# WaveFolder.net
KiCad netlist of a schematic drawn in EAGLE
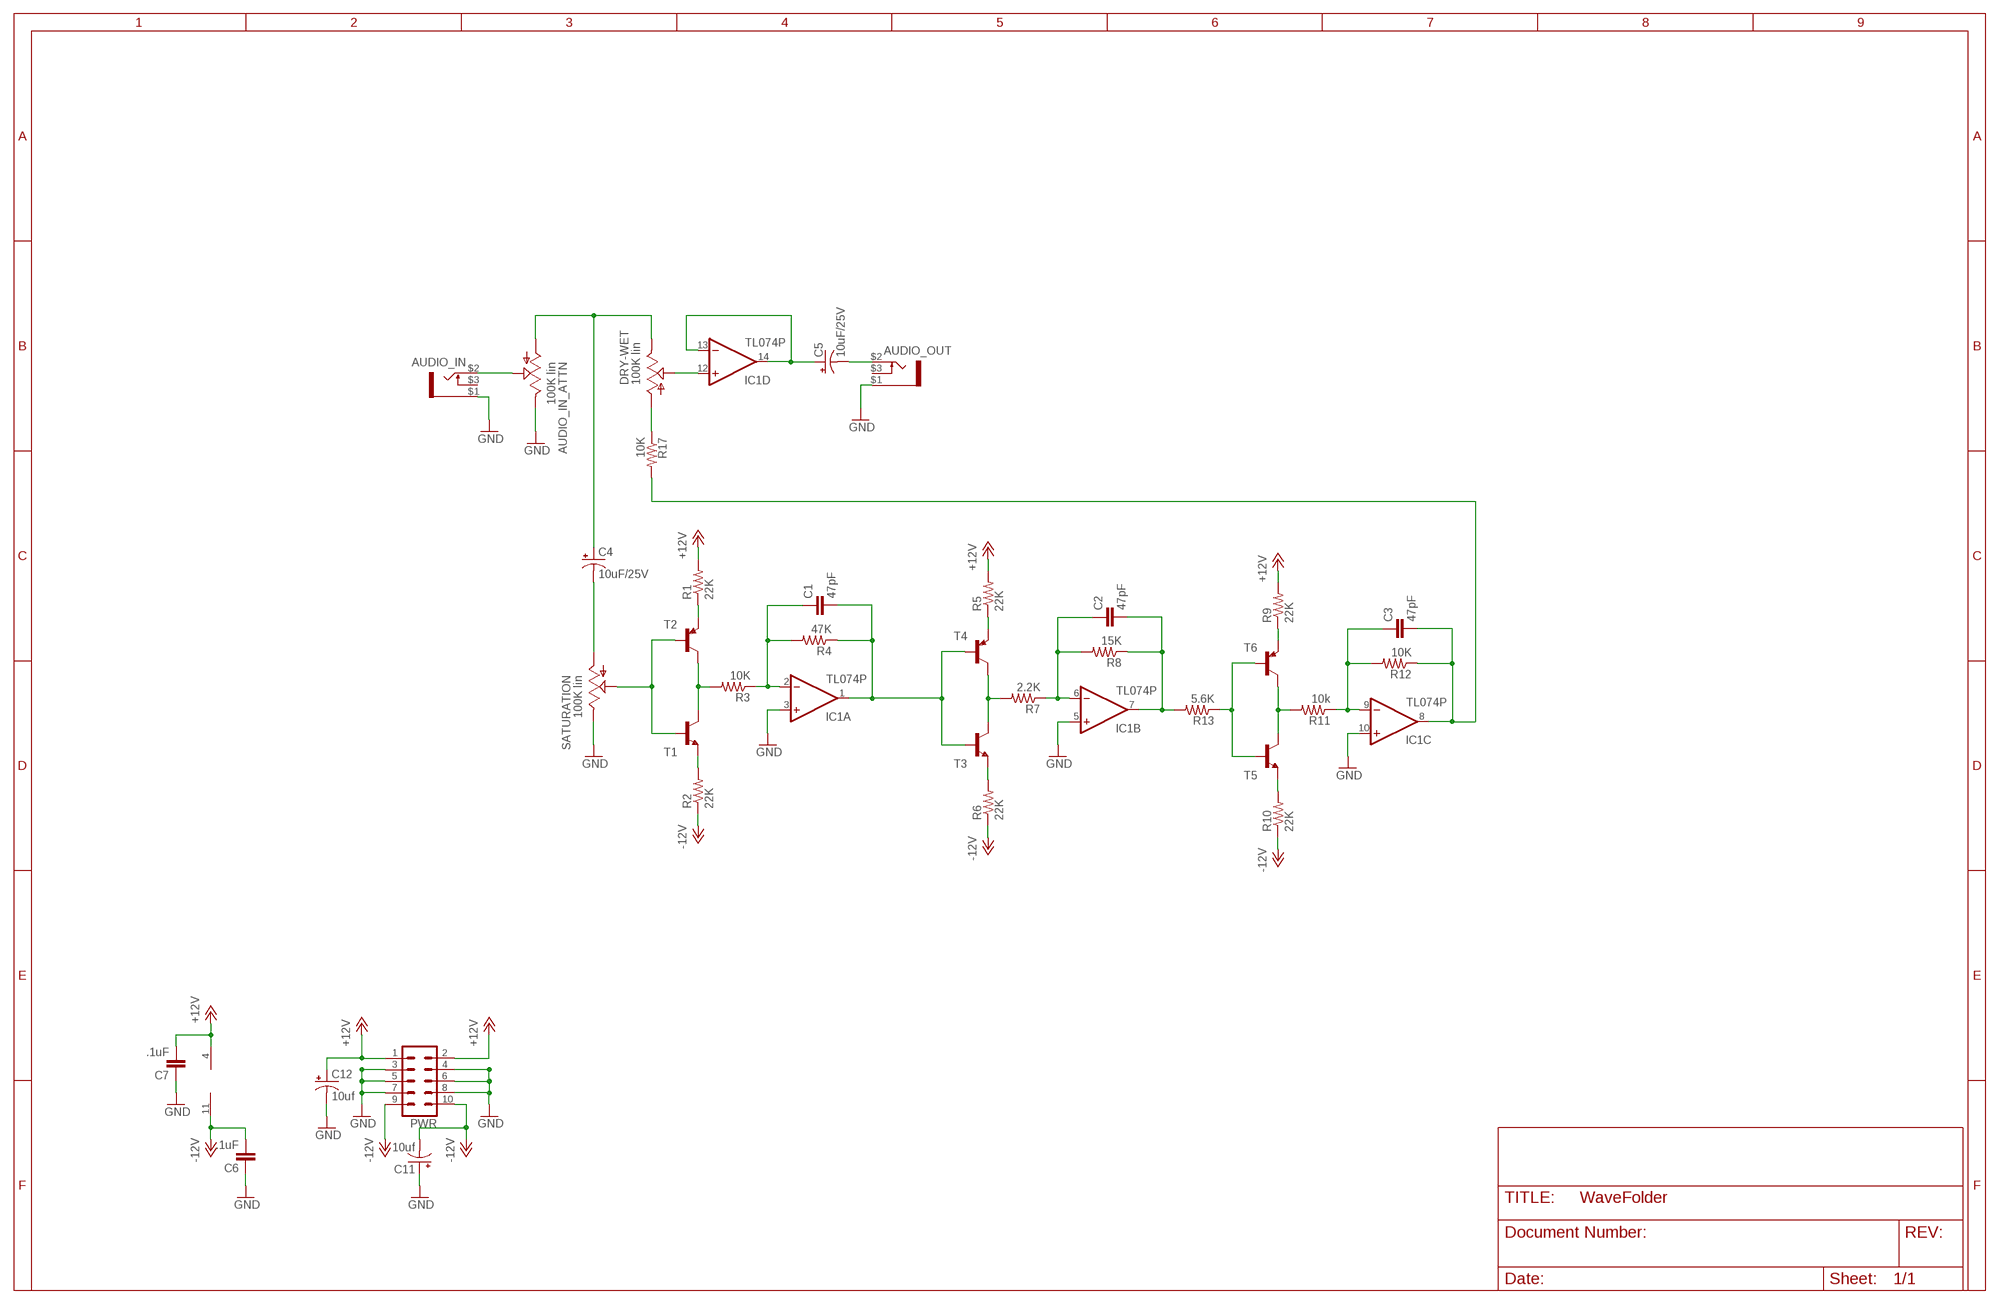
[diagram p0: schematic, sheet 1]

(export (version "E")
  (design (tool "Eeschema 10.0.6"))
  (components
    (comp (ref "AUDIO_IN")
      (value "PJ-323PJ-323")
      (footprint "eagle-import:PJ-323")
      (libsource (lib "eagle-import") (part "PJ-323PJ-323"))
    )
    (comp (ref "AUDIO_IN_ATTN")
      (value "100K lin")
      (footprint "eagle-import:EVUF")
      (libsource (lib "eagle-import") (part "RIGHT-ANGLE-POTA"))
    )
    (comp (ref "AUDIO_OUT")
      (value "PJ-323PJ-323")
      (footprint "eagle-import:PJ-323")
      (libsource (lib "eagle-import") (part "PJ-323PJ-323"))
    )
    (comp (ref "C1")
      (value "47pF")
      (footprint "eagle-import:C025-024X044")
      (libsource (lib "eagle-import") (part "C-EU025-024X044"))
    )
    (comp (ref "C2")
      (value "47pF")
      (footprint "eagle-import:C025-024X044")
      (libsource (lib "eagle-import") (part "C-EU025-024X044"))
    )
    (comp (ref "C3")
      (value "47pF")
      (footprint "eagle-import:C025-024X044")
      (libsource (lib "eagle-import") (part "C-EU025-024X044"))
    )
    (comp (ref "C4")
      (value "10uF/25V")
      (footprint "eagle-import:E2,5-6")
      (libsource (lib "eagle-import") (part "CPOL-USE2.5-6"))
    )
    (comp (ref "C5")
      (value "10uF/25V")
      (footprint "eagle-import:E2,5-6")
      (libsource (lib "eagle-import") (part "CPOL-USE2.5-6"))
    )
    (comp (ref "C6")
      (value ".1uF")
      (footprint "eagle-import:C025-024X044")
      (libsource (lib "eagle-import") (part "C-EU025-024X044"))
    )
    (comp (ref "C7")
      (value ".1uF")
      (footprint "eagle-import:C025-024X044")
      (libsource (lib "eagle-import") (part "C-EU025-024X044"))
    )
    (comp (ref "C11")
      (value "10uf")
      (footprint "eagle-import:E2,5-5")
      (libsource (lib "eagle-import") (part "resistor_CPOL-USE2.5-5"))
    )
    (comp (ref "C12")
      (value "10uf")
      (footprint "eagle-import:E2,5-5")
      (libsource (lib "eagle-import") (part "resistor_CPOL-USE2.5-5"))
    )
    (comp (ref "DRY-WET")
      (value "100K lin")
      (footprint "eagle-import:EVUF")
      (libsource (lib "eagle-import") (part "RIGHT-ANGLE-POTA"))
    )
    (comp (ref "IC1")
      (value "TL074P")
      (footprint "eagle-import:DIL14")
      (libsource (lib "eagle-import") (part "TL074P"))
    )
    (comp (ref "PWR")
      (value "ML10")
      (footprint "eagle-import:ML10")
      (libsource (lib "eagle-import") (part "ML10"))
    )
    (comp (ref "R1")
      (value "22K")
      (footprint "eagle-import:0207_7")
      (libsource (lib "eagle-import") (part "R-US_0207/7"))
    )
    (comp (ref "R2")
      (value "22K")
      (footprint "eagle-import:0207_7")
      (libsource (lib "eagle-import") (part "R-US_0207/7"))
    )
    (comp (ref "R3")
      (value "10K")
      (footprint "eagle-import:0207_7")
      (libsource (lib "eagle-import") (part "R-US_0207/7"))
    )
    (comp (ref "R4")
      (value "47K")
      (footprint "eagle-import:0207_7")
      (libsource (lib "eagle-import") (part "R-US_0207/7"))
    )
    (comp (ref "R5")
      (value "22K")
      (footprint "eagle-import:0207_7")
      (libsource (lib "eagle-import") (part "R-US_0207/7"))
    )
    (comp (ref "R6")
      (value "22K")
      (footprint "eagle-import:0207_7")
      (libsource (lib "eagle-import") (part "R-US_0207/7"))
    )
    (comp (ref "R7")
      (value "2.2K")
      (footprint "eagle-import:0207_7")
      (libsource (lib "eagle-import") (part "R-US_0207/7"))
    )
    (comp (ref "R8")
      (value "15K")
      (footprint "eagle-import:0207_7")
      (libsource (lib "eagle-import") (part "R-US_0207/7"))
    )
    (comp (ref "R9")
      (value "22K")
      (footprint "eagle-import:0207_7")
      (libsource (lib "eagle-import") (part "R-US_0207/7"))
    )
    (comp (ref "R10")
      (value "22K")
      (footprint "eagle-import:0207_7")
      (libsource (lib "eagle-import") (part "R-US_0207/7"))
    )
    (comp (ref "R11")
      (value "10k")
      (footprint "eagle-import:0207_7")
      (libsource (lib "eagle-import") (part "R-US_0207/7"))
    )
    (comp (ref "R12")
      (value "10K")
      (footprint "eagle-import:0207_7")
      (libsource (lib "eagle-import") (part "R-US_0207/7"))
    )
    (comp (ref "R13")
      (value "5.6K")
      (footprint "eagle-import:0207_7")
      (libsource (lib "eagle-import") (part "R-US_0207/7"))
    )
    (comp (ref "R17")
      (value "10K")
      (footprint "eagle-import:0207_7")
      (libsource (lib "eagle-import") (part "R-US_0207/7"))
    )
    (comp (ref "SATURATION")
      (value "100K lin")
      (footprint "eagle-import:EVUF")
      (libsource (lib "eagle-import") (part "RIGHT-ANGLE-POTA"))
    )
    (comp (ref "T1")
      (value "2N3904-NPN-TO92-EBC")
      (footprint "eagle-import:TO92-EBC")
      (libsource (lib "eagle-import") (part "-NPN-TO92-EBC2N3904"))
    )
    (comp (ref "T2")
      (value "2N3906-PNP-TO92-EBC")
      (footprint "eagle-import:TO92-EBC")
      (libsource (lib "eagle-import") (part "-PNP-TO92-EBC2N3906"))
    )
    (comp (ref "T3")
      (value "2N3904-NPN-TO92-EBC")
      (footprint "eagle-import:TO92-EBC")
      (libsource (lib "eagle-import") (part "-NPN-TO92-EBC2N3904"))
    )
    (comp (ref "T4")
      (value "2N3906-PNP-TO92-EBC")
      (footprint "eagle-import:TO92-EBC")
      (libsource (lib "eagle-import") (part "-PNP-TO92-EBC2N3906"))
    )
    (comp (ref "T5")
      (value "2N3904-NPN-TO92-EBC")
      (footprint "eagle-import:TO92-EBC")
      (libsource (lib "eagle-import") (part "-NPN-TO92-EBC2N3904"))
    )
    (comp (ref "T6")
      (value "2N3906-PNP-TO92-EBC")
      (footprint "eagle-import:TO92-EBC")
      (libsource (lib "eagle-import") (part "-PNP-TO92-EBC2N3906"))
    )
  )
  (nets
    (net (code "1") (name "+12V") (class "Default")
      (node (ref "C12") (pin "+") (pinfunction "+_+") (pintype "passive"))
      (node (ref "C7") (pin "2") (pinfunction "2_2") (pintype "passive"))
      (node (ref "IC1") (pin "4") (pinfunction "V+_4") (pintype "power_in"))
      (node (ref "PWR") (pin "1") (pinfunction "1_1") (pintype "passive"))
      (node (ref "PWR") (pin "2") (pinfunction "2_2") (pintype "passive"))
      (node (ref "R1") (pin "2") (pinfunction "2_2") (pintype "passive"))
      (node (ref "R5") (pin "2") (pinfunction "2_2") (pintype "passive"))
      (node (ref "R9") (pin "2") (pinfunction "2_2") (pintype "passive"))
    )
    (net (code "2") (name "-12V") (class "Default")
      (node (ref "C11") (pin "-") (pinfunction "-_-") (pintype "passive"))
      (node (ref "C6") (pin "2") (pinfunction "2_2") (pintype "passive"))
      (node (ref "IC1") (pin "11") (pinfunction "V-_11") (pintype "power_in"))
      (node (ref "PWR") (pin "10") (pinfunction "10_10") (pintype "passive"))
      (node (ref "PWR") (pin "9") (pinfunction "9_9") (pintype "passive"))
      (node (ref "R10") (pin "1") (pinfunction "1_1") (pintype "passive"))
      (node (ref "R2") (pin "1") (pinfunction "1_1") (pintype "passive"))
      (node (ref "R6") (pin "1") (pinfunction "1_1") (pintype "passive"))
    )
    (net (code "3") (name "GND") (class "Default")
      (node (ref "AUDIO_IN") (pin "$1") (pinfunction "3_$1") (pintype "passive"))
      (node (ref "AUDIO_IN_ATTN") (pin "3") (pinfunction "E_3") (pintype "passive"))
      (node (ref "AUDIO_OUT") (pin "$1") (pinfunction "3_$1") (pintype "passive"))
      (node (ref "C11") (pin "+") (pinfunction "+_+") (pintype "passive"))
      (node (ref "C12") (pin "-") (pinfunction "-_-") (pintype "passive"))
      (node (ref "C6") (pin "1") (pinfunction "1_1") (pintype "passive"))
      (node (ref "C7") (pin "1") (pinfunction "1_1") (pintype "passive"))
      (node (ref "IC1") (pin "10") (pinfunction "+IN_10") (pintype "input"))
      (node (ref "IC1") (pin "3") (pinfunction "+IN_3") (pintype "input"))
      (node (ref "IC1") (pin "5") (pinfunction "+IN_5") (pintype "input"))
      (node (ref "PWR") (pin "3") (pinfunction "3_3") (pintype "passive"))
      (node (ref "PWR") (pin "4") (pinfunction "4_4") (pintype "passive"))
      (node (ref "PWR") (pin "5") (pinfunction "5_5") (pintype "passive"))
      (node (ref "PWR") (pin "6") (pinfunction "6_6") (pintype "passive"))
      (node (ref "PWR") (pin "7") (pinfunction "7_7") (pintype "passive"))
      (node (ref "PWR") (pin "8") (pinfunction "8_8") (pintype "passive"))
      (node (ref "SATURATION") (pin "3") (pinfunction "E_3") (pintype "passive"))
    )
    (net (code "4") (name "Net-(AUDIO_IN-1)") (class "Default")
      (node (ref "AUDIO_IN") (pin "$2") (pinfunction "1_$2") (pintype "passive"))
      (node (ref "AUDIO_IN_ATTN") (pin "2") (pinfunction "S_2") (pintype "passive"))
    )
    (net (code "5") (name "Net-(AUDIO_IN_ATTN-A)") (class "Default")
      (node (ref "AUDIO_IN_ATTN") (pin "1") (pinfunction "A_1") (pintype "passive"))
      (node (ref "C4") (pin "+") (pinfunction "+_+") (pintype "passive"))
      (node (ref "DRY-WET") (pin "3") (pinfunction "E_3") (pintype "passive"))
    )
    (net (code "6") (name "Net-(AUDIO_OUT-1)") (class "Default")
      (node (ref "AUDIO_OUT") (pin "$2") (pinfunction "1_$2") (pintype "passive"))
      (node (ref "C5") (pin "-") (pinfunction "-_-") (pintype "passive"))
    )
    (net (code "7") (name "Net-(DRY-WET-A)") (class "Default")
      (node (ref "DRY-WET") (pin "1") (pinfunction "A_1") (pintype "passive"))
      (node (ref "R17") (pin "1") (pinfunction "1_1") (pintype "passive"))
    )
    (net (code "8") (name "Net-(DRY-WET-S)") (class "Default")
      (node (ref "DRY-WET") (pin "2") (pinfunction "S_2") (pintype "passive"))
      (node (ref "IC1") (pin "12") (pinfunction "+IN_12") (pintype "input"))
    )
    (net (code "9") (name "Net-(IC1A--IN)") (class "Default")
      (node (ref "C1") (pin "1") (pinfunction "1_1") (pintype "passive"))
      (node (ref "IC1") (pin "2") (pinfunction "-IN_2") (pintype "input"))
      (node (ref "R3") (pin "1") (pinfunction "1_1") (pintype "passive"))
      (node (ref "R4") (pin "2") (pinfunction "2_2") (pintype "passive"))
    )
    (net (code "10") (name "Net-(IC1A-OUT)") (class "Default")
      (node (ref "C1") (pin "2") (pinfunction "2_2") (pintype "passive"))
      (node (ref "IC1") (pin "1") (pinfunction "OUT_1") (pintype "output"))
      (node (ref "R4") (pin "1") (pinfunction "1_1") (pintype "passive"))
      (node (ref "T3") (pin "B") (pinfunction "B_B") (pintype "passive"))
      (node (ref "T4") (pin "B") (pinfunction "B_B") (pintype "passive"))
    )
    (net (code "11") (name "Net-(IC1B--IN)") (class "Default")
      (node (ref "C2") (pin "1") (pinfunction "1_1") (pintype "passive"))
      (node (ref "IC1") (pin "6") (pinfunction "-IN_6") (pintype "input"))
      (node (ref "R7") (pin "1") (pinfunction "1_1") (pintype "passive"))
      (node (ref "R8") (pin "2") (pinfunction "2_2") (pintype "passive"))
    )
    (net (code "12") (name "Net-(IC1B-OUT)") (class "Default")
      (node (ref "C2") (pin "2") (pinfunction "2_2") (pintype "passive"))
      (node (ref "IC1") (pin "7") (pinfunction "OUT_7") (pintype "output"))
      (node (ref "R13") (pin "2") (pinfunction "2_2") (pintype "passive"))
      (node (ref "R8") (pin "1") (pinfunction "1_1") (pintype "passive"))
    )
    (net (code "13") (name "Net-(IC1C--IN)") (class "Default")
      (node (ref "C3") (pin "1") (pinfunction "1_1") (pintype "passive"))
      (node (ref "IC1") (pin "9") (pinfunction "-IN_9") (pintype "input"))
      (node (ref "R11") (pin "1") (pinfunction "1_1") (pintype "passive"))
      (node (ref "R12") (pin "2") (pinfunction "2_2") (pintype "passive"))
    )
    (net (code "14") (name "Net-(IC1C-OUT)") (class "Default")
      (node (ref "C3") (pin "2") (pinfunction "2_2") (pintype "passive"))
      (node (ref "IC1") (pin "8") (pinfunction "OUT_8") (pintype "output"))
      (node (ref "R12") (pin "1") (pinfunction "1_1") (pintype "passive"))
      (node (ref "R17") (pin "2") (pinfunction "2_2") (pintype "passive"))
    )
    (net (code "15") (name "Net-(IC1D--IN)") (class "Default")
      (node (ref "C5") (pin "+") (pinfunction "+_+") (pintype "passive"))
      (node (ref "IC1") (pin "13") (pinfunction "-IN_13") (pintype "input"))
      (node (ref "IC1") (pin "14") (pinfunction "OUT_14") (pintype "output"))
    )
    (net (code "16") (name "Net-(R1-Pad1)") (class "Default")
      (node (ref "R1") (pin "1") (pinfunction "1_1") (pintype "passive"))
      (node (ref "T2") (pin "E") (pinfunction "E_E") (pintype "passive"))
    )
    (net (code "17") (name "Net-(R2-Pad2)") (class "Default")
      (node (ref "R2") (pin "2") (pinfunction "2_2") (pintype "passive"))
      (node (ref "T1") (pin "E") (pinfunction "E_E") (pintype "passive"))
    )
    (net (code "18") (name "Net-(R3-Pad2)") (class "Default")
      (node (ref "R3") (pin "2") (pinfunction "2_2") (pintype "passive"))
      (node (ref "T1") (pin "C") (pinfunction "C_C") (pintype "passive"))
      (node (ref "T2") (pin "C") (pinfunction "C_C") (pintype "passive"))
    )
    (net (code "19") (name "Net-(R5-Pad1)") (class "Default")
      (node (ref "R5") (pin "1") (pinfunction "1_1") (pintype "passive"))
      (node (ref "T4") (pin "E") (pinfunction "E_E") (pintype "passive"))
    )
    (net (code "20") (name "Net-(R6-Pad2)") (class "Default")
      (node (ref "R6") (pin "2") (pinfunction "2_2") (pintype "passive"))
      (node (ref "T3") (pin "E") (pinfunction "E_E") (pintype "passive"))
    )
    (net (code "21") (name "Net-(R7-Pad2)") (class "Default")
      (node (ref "R7") (pin "2") (pinfunction "2_2") (pintype "passive"))
      (node (ref "T3") (pin "C") (pinfunction "C_C") (pintype "passive"))
      (node (ref "T4") (pin "C") (pinfunction "C_C") (pintype "passive"))
    )
    (net (code "22") (name "Net-(R9-Pad1)") (class "Default")
      (node (ref "R9") (pin "1") (pinfunction "1_1") (pintype "passive"))
      (node (ref "T6") (pin "E") (pinfunction "E_E") (pintype "passive"))
    )
    (net (code "23") (name "Net-(R10-Pad2)") (class "Default")
      (node (ref "R10") (pin "2") (pinfunction "2_2") (pintype "passive"))
      (node (ref "T5") (pin "E") (pinfunction "E_E") (pintype "passive"))
    )
    (net (code "24") (name "Net-(R11-Pad2)") (class "Default")
      (node (ref "R11") (pin "2") (pinfunction "2_2") (pintype "passive"))
      (node (ref "T5") (pin "C") (pinfunction "C_C") (pintype "passive"))
      (node (ref "T6") (pin "C") (pinfunction "C_C") (pintype "passive"))
    )
    (net (code "25") (name "Net-(R13-Pad1)") (class "Default")
      (node (ref "R13") (pin "1") (pinfunction "1_1") (pintype "passive"))
      (node (ref "T5") (pin "B") (pinfunction "B_B") (pintype "passive"))
      (node (ref "T6") (pin "B") (pinfunction "B_B") (pintype "passive"))
    )
    (net (code "26") (name "Net-(SATURATION-A)") (class "Default")
      (node (ref "C4") (pin "-") (pinfunction "-_-") (pintype "passive"))
      (node (ref "SATURATION") (pin "1") (pinfunction "A_1") (pintype "passive"))
    )
    (net (code "27") (name "Net-(SATURATION-S)") (class "Default")
      (node (ref "SATURATION") (pin "2") (pinfunction "S_2") (pintype "passive"))
      (node (ref "T1") (pin "B") (pinfunction "B_B") (pintype "passive"))
      (node (ref "T2") (pin "B") (pinfunction "B_B") (pintype "passive"))
    )
    (net (code "28") (name "unconnected-(AUDIO_IN-2-Pad$3)") (class "Default")
      (node (ref "AUDIO_IN") (pin "$3") (pinfunction "2_$3") (pintype "passive"))
    )
    (net (code "29") (name "unconnected-(AUDIO_OUT-2-Pad$3)") (class "Default")
      (node (ref "AUDIO_OUT") (pin "$3") (pinfunction "2_$3") (pintype "passive"))
    )
  )
)
